# escape_uno.net
KiCad netlist of a schematic drawn in EAGLE
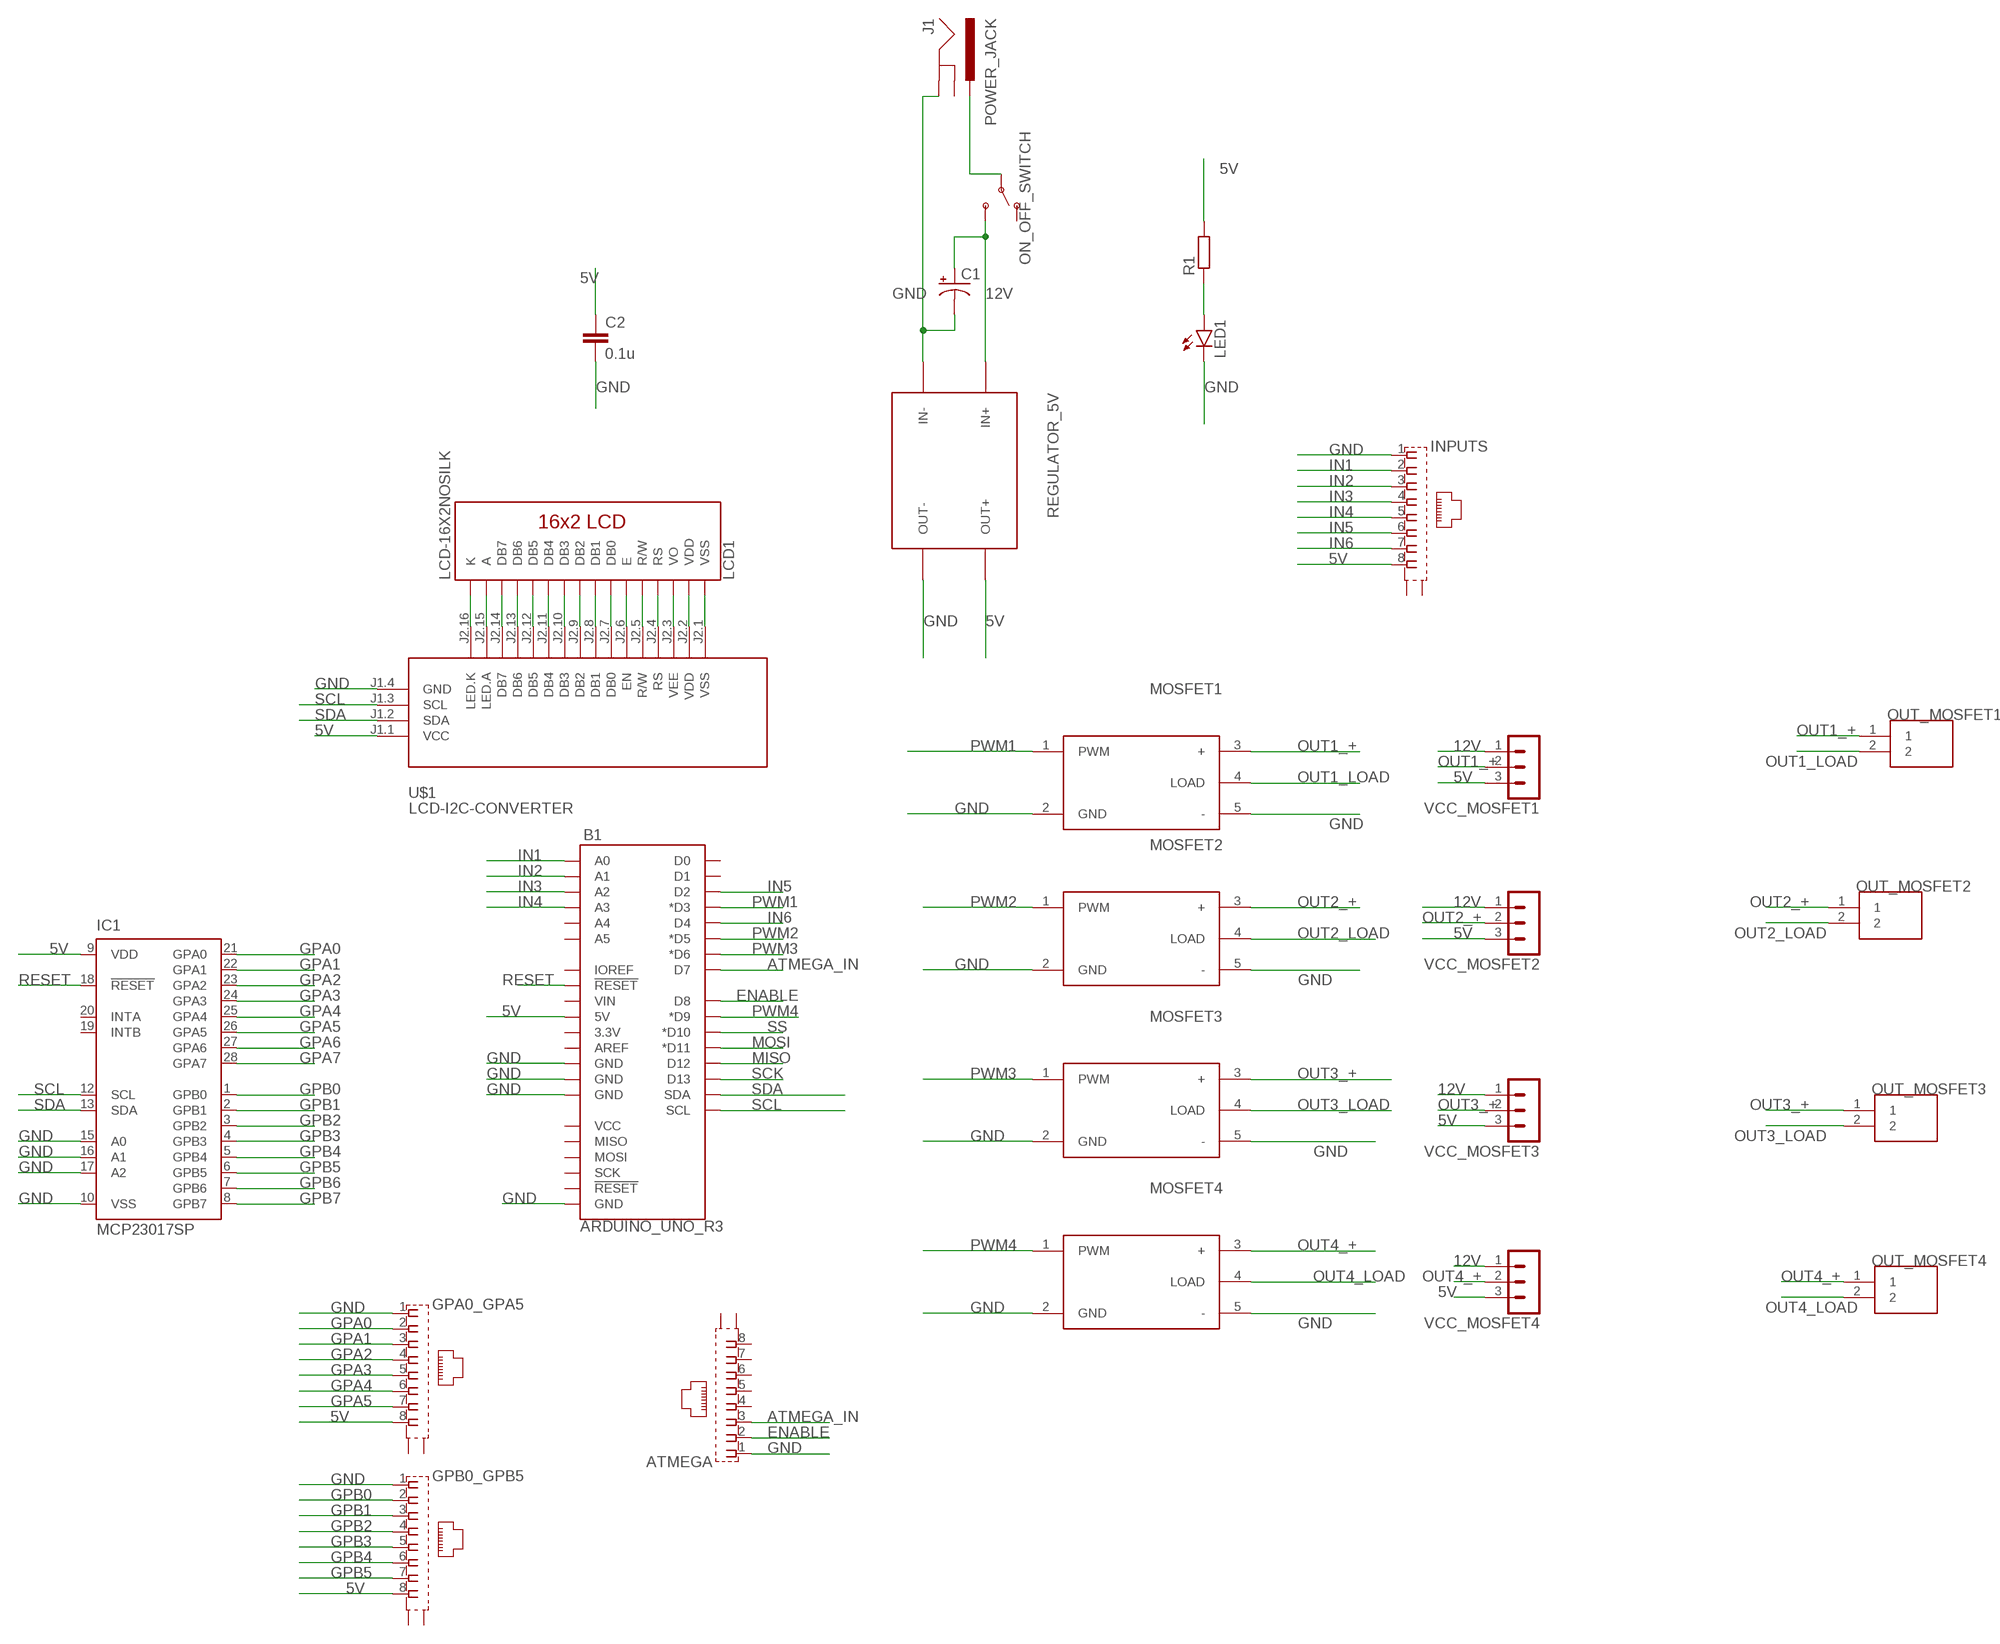
[diagram p0: schematic, sheet 1]

(export (version "E")
  (design (tool "Eeschema 10.0.6"))
  (components
    (comp (ref "ATMEGA")
      (value "GLX-S-88M")
      (footprint "eagle-import:GLX-S-88M")
      (libsource (lib "eagle-import") (part "GLX-S-88M"))
    )
    (comp (ref "B1")
      (value "ARDUINO_UNO_R3")
      (footprint "eagle-import:ARDUINO_R3")
      (libsource (lib "eagle-import") (part "ARDUINO_UNO_R3"))
    )
    (comp (ref "C1")
      (value "CPOL-USB45181C")
      (footprint "eagle-import:B45181C")
      (libsource (lib "eagle-import") (part "CPOL-USB45181C"))
    )
    (comp (ref "C2")
      (value "0.1u")
      (footprint "eagle-import:C025-025X050")
      (libsource (lib "eagle-import") (part "C-EU025-025X050"))
    )
    (comp (ref "GPA0_GPA5")
      (value "GLX-S-88M")
      (footprint "eagle-import:GLX-S-88M")
      (libsource (lib "eagle-import") (part "GLX-S-88M"))
    )
    (comp (ref "GPB0_GPB5")
      (value "GLX-S-88M")
      (footprint "eagle-import:GLX-S-88M")
      (libsource (lib "eagle-import") (part "GLX-S-88M"))
    )
    (comp (ref "IC1")
      (value "MCP23017SP")
      (footprint "eagle-import:DIL28-3")
      (fields (field (name "MF") "MICROCHIP") (field (name "MPN") "MCP23017-E/SP"))
      (libsource (lib "eagle-import") (part "MCP23017SP"))
    )
    (comp (ref "INPUTS")
      (value "GLX-S-88M")
      (footprint "eagle-import:GLX-S-88M")
      (libsource (lib "eagle-import") (part "GLX-S-88M"))
    )
    (comp (ref "J1")
      (value "POWER_JACK")
      (footprint "eagle-import:POWER_JACK_PTH")
      (libsource (lib "eagle-import") (part "POWER_JACK"))
    )
    (comp (ref "LCD1")
      (value "LCD-16X2NOSILK")
      (footprint "eagle-import:LCD-16X2_NOSILK")
      (libsource (lib "eagle-import") (part "LCD-16X2NOSILK"))
    )
    (comp (ref "LED1")
      (value "LED5MM")
      (footprint "eagle-import:LED5MM")
      (libsource (lib "eagle-import") (part "LED5MM"))
    )
    (comp (ref "MOSFET1")
      (value "SAMACSYS_PARTS_FR120N-ISOLATED-MOSFET-MOD")
      (footprint "eagle-import:SAMACSYS_PARTS_FR120N-ISOLATED-MOSFET-MOD")
      (libsource (lib "eagle-import") (part "SAMACSYS_PARTS_FR120N-ISOLATED-MOSFET-MOD"))
    )
    (comp (ref "MOSFET2")
      (value "SAMACSYS_PARTS_FR120N-ISOLATED-MOSFET-MOD")
      (footprint "eagle-import:SAMACSYS_PARTS_FR120N-ISOLATED-MOSFET-MOD")
      (libsource (lib "eagle-import") (part "SAMACSYS_PARTS_FR120N-ISOLATED-MOSFET-MOD"))
    )
    (comp (ref "MOSFET3")
      (value "SAMACSYS_PARTS_FR120N-ISOLATED-MOSFET-MOD")
      (footprint "eagle-import:SAMACSYS_PARTS_FR120N-ISOLATED-MOSFET-MOD")
      (libsource (lib "eagle-import") (part "SAMACSYS_PARTS_FR120N-ISOLATED-MOSFET-MOD"))
    )
    (comp (ref "MOSFET4")
      (value "SAMACSYS_PARTS_FR120N-ISOLATED-MOSFET-MOD")
      (footprint "eagle-import:SAMACSYS_PARTS_FR120N-ISOLATED-MOSFET-MOD")
      (libsource (lib "eagle-import") (part "SAMACSYS_PARTS_FR120N-ISOLATED-MOSFET-MOD"))
    )
    (comp (ref "ON_OFF_SWITCH")
      (value "SWITCH-SPDT-PTH-11.6X4.0MM-SHORT_LEADS")
      (footprint "eagle-import:SWITCH_SPDT_PTH_11.6X4.0MM")
      (libsource (lib "eagle-import") (part "SWITCH-SPDT-PTH-11.6X4.0MM-SHORT_LEADS"))
    )
    (comp (ref "OUT_MOSFET1")
      (value "TB006-508-02BE_TB006-508-02BE")
      (footprint "eagle-import:TB006-508-02BE_CUI_TB006-508-02BE")
      (fields (field (name "MF") "CUI Devices") (field (name "MP") "TB006-508-02BE"))
      (libsource (lib "eagle-import") (part "TB006-508-02BE_TB006-508-02BE"))
    )
    (comp (ref "OUT_MOSFET2")
      (value "TB006-508-02BE_TB006-508-02BE")
      (footprint "eagle-import:TB006-508-02BE_CUI_TB006-508-02BE")
      (fields (field (name "MF") "CUI Devices") (field (name "MP") "TB006-508-02BE"))
      (libsource (lib "eagle-import") (part "TB006-508-02BE_TB006-508-02BE"))
    )
    (comp (ref "OUT_MOSFET3")
      (value "TB006-508-02BE_TB006-508-02BE")
      (footprint "eagle-import:TB006-508-02BE_CUI_TB006-508-02BE")
      (fields (field (name "MF") "CUI Devices") (field (name "MP") "TB006-508-02BE"))
      (libsource (lib "eagle-import") (part "TB006-508-02BE_TB006-508-02BE"))
    )
    (comp (ref "OUT_MOSFET4")
      (value "TB006-508-02BE_TB006-508-02BE")
      (footprint "eagle-import:TB006-508-02BE_CUI_TB006-508-02BE")
      (fields (field (name "MF") "CUI Devices") (field (name "MP") "TB006-508-02BE"))
      (libsource (lib "eagle-import") (part "TB006-508-02BE_TB006-508-02BE"))
    )
    (comp (ref "R1")
      (value "R-EU_0207/10")
      (footprint "eagle-import:0207_10")
      (libsource (lib "eagle-import") (part "R-EU_0207/10"))
    )
    (comp (ref "REGULATOR_5V")
      (value "DIY-MODULES_DC-DC-STEP-DOWN-LM2596")
      (footprint "eagle-import:DIY-MODULES_DC-DC-STEP-DOWN-LM2596")
      (libsource (lib "eagle-import") (part "DIY-MODULES_DC-DC-STEP-DOWN-LM2596"))
    )
    (comp (ref "U$1")
      (value "LCD-I2C-CONVERTER")
      (footprint "eagle-import:LCD-I2C-CONVERTER")
      (libsource (lib "eagle-import") (part "LCD-I2C-CONVERTER"))
    )
    (comp (ref "VCC_MOSFET1")
      (value "MA03-1")
      (footprint "eagle-import:MA03-1")
      (libsource (lib "eagle-import") (part "MA03-1"))
    )
    (comp (ref "VCC_MOSFET2")
      (value "MA03-1")
      (footprint "eagle-import:MA03-1")
      (libsource (lib "eagle-import") (part "MA03-1"))
    )
    (comp (ref "VCC_MOSFET3")
      (value "MA03-1")
      (footprint "eagle-import:MA03-1")
      (libsource (lib "eagle-import") (part "MA03-1"))
    )
    (comp (ref "VCC_MOSFET4")
      (value "MA03-1")
      (footprint "eagle-import:MA03-1")
      (libsource (lib "eagle-import") (part "MA03-1"))
    )
  )
  (nets
    (net (code "1") (name "/5V") (class "Default")
      (node (ref "B1") (pin "5V") (pinfunction "5V_5V") (pintype "bidirectional"))
      (node (ref "C2") (pin "1") (pinfunction "1_1") (pintype "passive"))
      (node (ref "GPA0_GPA5") (pin "8") (pinfunction "8_8") (pintype "passive"))
      (node (ref "GPB0_GPB5") (pin "8") (pinfunction "8_8") (pintype "passive"))
      (node (ref "IC1") (pin "9") (pinfunction "VDD_9") (pintype "power_in"))
      (node (ref "INPUTS") (pin "8") (pinfunction "8_8") (pintype "passive"))
      (node (ref "R1") (pin "2") (pinfunction "2_2") (pintype "passive"))
      (node (ref "REGULATOR_5V") (pin "OUT+") (pinfunction "OUT+_OUT+") (pintype "bidirectional"))
      (node (ref "U$1") (pin "J1.1") (pinfunction "VCC_J1.1") (pintype "power_in"))
      (node (ref "VCC_MOSFET1") (pin "3") (pinfunction "3_3") (pintype "passive"))
      (node (ref "VCC_MOSFET2") (pin "3") (pinfunction "3_3") (pintype "passive"))
      (node (ref "VCC_MOSFET3") (pin "3") (pinfunction "3_3") (pintype "passive"))
      (node (ref "VCC_MOSFET4") (pin "3") (pinfunction "3_3") (pintype "passive"))
    )
    (net (code "2") (name "/12V") (class "Default")
      (node (ref "C1") (pin "+") (pinfunction "+_+") (pintype "passive"))
      (node (ref "ON_OFF_SWITCH") (pin "3") (pinfunction "S_3") (pintype "passive"))
      (node (ref "REGULATOR_5V") (pin "IN+") (pinfunction "IN+_IN+") (pintype "bidirectional"))
      (node (ref "VCC_MOSFET1") (pin "1") (pinfunction "1_1") (pintype "passive"))
      (node (ref "VCC_MOSFET2") (pin "1") (pinfunction "1_1") (pintype "passive"))
      (node (ref "VCC_MOSFET3") (pin "1") (pinfunction "1_1") (pintype "passive"))
      (node (ref "VCC_MOSFET4") (pin "1") (pinfunction "1_1") (pintype "passive"))
    )
    (net (code "3") (name "/ATMEGA_IN") (class "Default")
      (node (ref "ATMEGA") (pin "3") (pinfunction "3_3") (pintype "passive"))
      (node (ref "B1") (pin "D7") (pinfunction "D7_D7") (pintype "bidirectional"))
    )
    (net (code "4") (name "/ENABLE") (class "Default")
      (node (ref "ATMEGA") (pin "2") (pinfunction "2_2") (pintype "passive"))
      (node (ref "B1") (pin "D8") (pinfunction "D8_D8") (pintype "bidirectional"))
    )
    (net (code "5") (name "/GND") (class "Default")
      (node (ref "ATMEGA") (pin "1") (pinfunction "1_1") (pintype "passive"))
      (node (ref "B1") (pin "GND@1") (pinfunction "GND_GND@1") (pintype "bidirectional"))
      (node (ref "B1") (pin "GND@2") (pinfunction "GND_GND@2") (pintype "bidirectional"))
      (node (ref "B1") (pin "GND@3") (pinfunction "GND_GND@3") (pintype "bidirectional"))
      (node (ref "B1") (pin "GND@4") (pinfunction "GND_GND@4") (pintype "bidirectional"))
      (node (ref "C1") (pin "-") (pinfunction "-_-") (pintype "passive"))
      (node (ref "C2") (pin "2") (pinfunction "2_2") (pintype "passive"))
      (node (ref "GPA0_GPA5") (pin "1") (pinfunction "1_1") (pintype "passive"))
      (node (ref "GPB0_GPB5") (pin "1") (pinfunction "1_1") (pintype "passive"))
      (node (ref "IC1") (pin "10") (pinfunction "VSS_10") (pintype "power_in"))
      (node (ref "IC1") (pin "15") (pinfunction "A0_15") (pintype "input"))
      (node (ref "IC1") (pin "16") (pinfunction "A1_16") (pintype "input"))
      (node (ref "IC1") (pin "17") (pinfunction "A2_17") (pintype "input"))
      (node (ref "INPUTS") (pin "1") (pinfunction "1_1") (pintype "passive"))
      (node (ref "J1") (pin "GND") (pinfunction "GND_GND") (pintype "bidirectional"))
      (node (ref "LED1") (pin "K") (pinfunction "C_K") (pintype "passive"))
      (node (ref "MOSFET1") (pin "2") (pinfunction "GND_2") (pintype "bidirectional"))
      (node (ref "MOSFET1") (pin "5") (pinfunction "-_5") (pintype "bidirectional"))
      (node (ref "MOSFET2") (pin "2") (pinfunction "GND_2") (pintype "bidirectional"))
      (node (ref "MOSFET2") (pin "5") (pinfunction "-_5") (pintype "bidirectional"))
      (node (ref "MOSFET3") (pin "2") (pinfunction "GND_2") (pintype "bidirectional"))
      (node (ref "MOSFET3") (pin "5") (pinfunction "-_5") (pintype "bidirectional"))
      (node (ref "MOSFET4") (pin "2") (pinfunction "GND_2") (pintype "bidirectional"))
      (node (ref "MOSFET4") (pin "5") (pinfunction "-_5") (pintype "bidirectional"))
      (node (ref "REGULATOR_5V") (pin "IN-") (pinfunction "IN-_IN-") (pintype "bidirectional"))
      (node (ref "REGULATOR_5V") (pin "OUT-") (pinfunction "OUT-_OUT-") (pintype "bidirectional"))
      (node (ref "U$1") (pin "J1.4") (pinfunction "GND_J1.4") (pintype "power_in"))
    )
    (net (code "6") (name "/GPA0") (class "Default")
      (node (ref "GPA0_GPA5") (pin "2") (pinfunction "2_2") (pintype "passive"))
      (node (ref "IC1") (pin "21") (pinfunction "GPA0_21") (pintype "bidirectional"))
    )
    (net (code "7") (name "/GPA1") (class "Default")
      (node (ref "GPA0_GPA5") (pin "3") (pinfunction "3_3") (pintype "passive"))
      (node (ref "IC1") (pin "22") (pinfunction "GPA1_22") (pintype "bidirectional"))
    )
    (net (code "8") (name "/GPA2") (class "Default")
      (node (ref "GPA0_GPA5") (pin "4") (pinfunction "4_4") (pintype "passive"))
      (node (ref "IC1") (pin "23") (pinfunction "GPA2_23") (pintype "bidirectional"))
    )
    (net (code "9") (name "/GPA3") (class "Default")
      (node (ref "GPA0_GPA5") (pin "5") (pinfunction "5_5") (pintype "passive"))
      (node (ref "IC1") (pin "24") (pinfunction "GPA3_24") (pintype "bidirectional"))
    )
    (net (code "10") (name "/GPA4") (class "Default")
      (node (ref "GPA0_GPA5") (pin "6") (pinfunction "6_6") (pintype "passive"))
      (node (ref "IC1") (pin "25") (pinfunction "GPA4_25") (pintype "bidirectional"))
    )
    (net (code "11") (name "/GPA5") (class "Default")
      (node (ref "GPA0_GPA5") (pin "7") (pinfunction "7_7") (pintype "passive"))
      (node (ref "IC1") (pin "26") (pinfunction "GPA5_26") (pintype "bidirectional"))
    )
    (net (code "12") (name "/GPA6") (class "Default")
      (node (ref "IC1") (pin "27") (pinfunction "GPA6_27") (pintype "bidirectional"))
    )
    (net (code "13") (name "/GPA7") (class "Default")
      (node (ref "IC1") (pin "28") (pinfunction "GPA7_28") (pintype "bidirectional"))
    )
    (net (code "14") (name "/GPB0") (class "Default")
      (node (ref "GPB0_GPB5") (pin "2") (pinfunction "2_2") (pintype "passive"))
      (node (ref "IC1") (pin "1") (pinfunction "GPB0_1") (pintype "bidirectional"))
    )
    (net (code "15") (name "/GPB1") (class "Default")
      (node (ref "GPB0_GPB5") (pin "3") (pinfunction "3_3") (pintype "passive"))
      (node (ref "IC1") (pin "2") (pinfunction "GPB1_2") (pintype "bidirectional"))
    )
    (net (code "16") (name "/GPB2") (class "Default")
      (node (ref "GPB0_GPB5") (pin "4") (pinfunction "4_4") (pintype "passive"))
      (node (ref "IC1") (pin "3") (pinfunction "GPB2_3") (pintype "bidirectional"))
    )
    (net (code "17") (name "/GPB3") (class "Default")
      (node (ref "GPB0_GPB5") (pin "5") (pinfunction "5_5") (pintype "passive"))
      (node (ref "IC1") (pin "4") (pinfunction "GPB3_4") (pintype "bidirectional"))
    )
    (net (code "18") (name "/GPB4") (class "Default")
      (node (ref "GPB0_GPB5") (pin "6") (pinfunction "6_6") (pintype "passive"))
      (node (ref "IC1") (pin "5") (pinfunction "GPB4_5") (pintype "bidirectional"))
    )
    (net (code "19") (name "/GPB5") (class "Default")
      (node (ref "GPB0_GPB5") (pin "7") (pinfunction "7_7") (pintype "passive"))
      (node (ref "IC1") (pin "6") (pinfunction "GPB5_6") (pintype "bidirectional"))
    )
    (net (code "20") (name "/GPB6") (class "Default")
      (node (ref "IC1") (pin "7") (pinfunction "GPB6_7") (pintype "bidirectional"))
    )
    (net (code "21") (name "/GPB7") (class "Default")
      (node (ref "IC1") (pin "8") (pinfunction "GPB7_8") (pintype "bidirectional"))
    )
    (net (code "22") (name "/IN1") (class "Default")
      (node (ref "B1") (pin "A0") (pinfunction "A0_A0") (pintype "bidirectional"))
      (node (ref "INPUTS") (pin "2") (pinfunction "2_2") (pintype "passive"))
    )
    (net (code "23") (name "/IN2") (class "Default")
      (node (ref "B1") (pin "A1") (pinfunction "A1_A1") (pintype "bidirectional"))
      (node (ref "INPUTS") (pin "3") (pinfunction "3_3") (pintype "passive"))
    )
    (net (code "24") (name "/IN3") (class "Default")
      (node (ref "B1") (pin "A2") (pinfunction "A2_A2") (pintype "bidirectional"))
      (node (ref "INPUTS") (pin "4") (pinfunction "4_4") (pintype "passive"))
    )
    (net (code "25") (name "/IN4") (class "Default")
      (node (ref "B1") (pin "A3") (pinfunction "A3_A3") (pintype "bidirectional"))
      (node (ref "INPUTS") (pin "5") (pinfunction "5_5") (pintype "passive"))
    )
    (net (code "26") (name "/IN5") (class "Default")
      (node (ref "B1") (pin "D2") (pinfunction "D2_D2") (pintype "bidirectional"))
      (node (ref "INPUTS") (pin "6") (pinfunction "6_6") (pintype "passive"))
    )
    (net (code "27") (name "/IN6") (class "Default")
      (node (ref "B1") (pin "D4") (pinfunction "D4_D4") (pintype "bidirectional"))
      (node (ref "INPUTS") (pin "7") (pinfunction "7_7") (pintype "passive"))
    )
    (net (code "28") (name "/MISO") (class "Default")
      (node (ref "B1") (pin "D12") (pinfunction "D12_D12") (pintype "bidirectional"))
    )
    (net (code "29") (name "/MOSI") (class "Default")
      (node (ref "B1") (pin "D11") (pinfunction "*D11_D11") (pintype "bidirectional"))
    )
    (net (code "30") (name "/OUT1_+") (class "Default")
      (node (ref "MOSFET1") (pin "3") (pinfunction "+_3") (pintype "bidirectional"))
      (node (ref "OUT_MOSFET1") (pin "1") (pinfunction "1_1") (pintype "passive"))
      (node (ref "VCC_MOSFET1") (pin "2") (pinfunction "2_2") (pintype "passive"))
    )
    (net (code "31") (name "/OUT1_LOAD") (class "Default")
      (node (ref "MOSFET1") (pin "4") (pinfunction "LOAD_4") (pintype "bidirectional"))
      (node (ref "OUT_MOSFET1") (pin "2") (pinfunction "2_2") (pintype "passive"))
    )
    (net (code "32") (name "/OUT2_+") (class "Default")
      (node (ref "MOSFET2") (pin "3") (pinfunction "+_3") (pintype "bidirectional"))
      (node (ref "OUT_MOSFET2") (pin "1") (pinfunction "1_1") (pintype "passive"))
      (node (ref "VCC_MOSFET2") (pin "2") (pinfunction "2_2") (pintype "passive"))
    )
    (net (code "33") (name "/OUT2_LOAD") (class "Default")
      (node (ref "MOSFET2") (pin "4") (pinfunction "LOAD_4") (pintype "bidirectional"))
      (node (ref "OUT_MOSFET2") (pin "2") (pinfunction "2_2") (pintype "passive"))
    )
    (net (code "34") (name "/OUT3_+") (class "Default")
      (node (ref "MOSFET3") (pin "3") (pinfunction "+_3") (pintype "bidirectional"))
      (node (ref "OUT_MOSFET3") (pin "1") (pinfunction "1_1") (pintype "passive"))
      (node (ref "VCC_MOSFET3") (pin "2") (pinfunction "2_2") (pintype "passive"))
    )
    (net (code "35") (name "/OUT3_LOAD") (class "Default")
      (node (ref "MOSFET3") (pin "4") (pinfunction "LOAD_4") (pintype "bidirectional"))
      (node (ref "OUT_MOSFET3") (pin "2") (pinfunction "2_2") (pintype "passive"))
    )
    (net (code "36") (name "/OUT4_+") (class "Default")
      (node (ref "MOSFET4") (pin "3") (pinfunction "+_3") (pintype "bidirectional"))
      (node (ref "OUT_MOSFET4") (pin "1") (pinfunction "1_1") (pintype "passive"))
      (node (ref "VCC_MOSFET4") (pin "2") (pinfunction "2_2") (pintype "passive"))
    )
    (net (code "37") (name "/OUT4_LOAD") (class "Default")
      (node (ref "MOSFET4") (pin "4") (pinfunction "LOAD_4") (pintype "bidirectional"))
      (node (ref "OUT_MOSFET4") (pin "2") (pinfunction "2_2") (pintype "passive"))
    )
    (net (code "38") (name "/PWM1") (class "Default")
      (node (ref "B1") (pin "D3") (pinfunction "*D3_D3") (pintype "bidirectional"))
      (node (ref "MOSFET1") (pin "1") (pinfunction "PWM_1") (pintype "bidirectional"))
    )
    (net (code "39") (name "/PWM2") (class "Default")
      (node (ref "B1") (pin "D5") (pinfunction "*D5_D5") (pintype "bidirectional"))
      (node (ref "MOSFET2") (pin "1") (pinfunction "PWM_1") (pintype "bidirectional"))
    )
    (net (code "40") (name "/PWM3") (class "Default")
      (node (ref "B1") (pin "D6") (pinfunction "*D6_D6") (pintype "bidirectional"))
      (node (ref "MOSFET3") (pin "1") (pinfunction "PWM_1") (pintype "bidirectional"))
    )
    (net (code "41") (name "/PWM4") (class "Default")
      (node (ref "B1") (pin "D9") (pinfunction "*D9_D9") (pintype "bidirectional"))
      (node (ref "MOSFET4") (pin "1") (pinfunction "PWM_1") (pintype "bidirectional"))
    )
    (net (code "42") (name "/RESET") (class "Default")
      (node (ref "B1") (pin "RESET@1") (pinfunction "~{RESET}_RESET@1") (pintype "bidirectional"))
      (node (ref "IC1") (pin "18") (pinfunction "~{RESET}_18") (pintype "input"))
    )
    (net (code "43") (name "/SCK") (class "Default")
      (node (ref "B1") (pin "D13") (pinfunction "D13_D13") (pintype "bidirectional"))
    )
    (net (code "44") (name "/SCL") (class "Default")
      (node (ref "B1") (pin "SCL") (pinfunction "SCL_SCL") (pintype "bidirectional"))
      (node (ref "IC1") (pin "12") (pinfunction "SCL_12") (pintype "input"))
      (node (ref "U$1") (pin "J1.3") (pinfunction "SCL_J1.3") (pintype "bidirectional"))
    )
    (net (code "45") (name "/SDA") (class "Default")
      (node (ref "B1") (pin "SDA") (pinfunction "SDA_SDA") (pintype "bidirectional"))
      (node (ref "IC1") (pin "13") (pinfunction "SDA_13") (pintype "bidirectional"))
      (node (ref "U$1") (pin "J1.2") (pinfunction "SDA_J1.2") (pintype "bidirectional"))
    )
    (net (code "46") (name "/SS") (class "Default")
      (node (ref "B1") (pin "D10") (pinfunction "*D10_D10") (pintype "bidirectional"))
    )
    (net (code "47") (name "Net-(LCD1-A)") (class "Default")
      (node (ref "LCD1") (pin "15") (pinfunction "A_15") (pintype "power_in"))
      (node (ref "U$1") (pin "J2.15") (pinfunction "LED.A_J2.15") (pintype "bidirectional"))
    )
    (net (code "48") (name "Net-(LCD1-DB0)") (class "Default")
      (node (ref "LCD1") (pin "7") (pinfunction "DB0_7") (pintype "bidirectional"))
      (node (ref "U$1") (pin "J2.7") (pinfunction "DB0_J2.7") (pintype "bidirectional"))
    )
    (net (code "49") (name "Net-(LCD1-DB1)") (class "Default")
      (node (ref "LCD1") (pin "8") (pinfunction "DB1_8") (pintype "bidirectional"))
      (node (ref "U$1") (pin "J2.8") (pinfunction "DB1_J2.8") (pintype "bidirectional"))
    )
    (net (code "50") (name "Net-(LCD1-DB2)") (class "Default")
      (node (ref "LCD1") (pin "9") (pinfunction "DB2_9") (pintype "bidirectional"))
      (node (ref "U$1") (pin "J2.9") (pinfunction "DB2_J2.9") (pintype "bidirectional"))
    )
    (net (code "51") (name "Net-(LCD1-DB3)") (class "Default")
      (node (ref "LCD1") (pin "10") (pinfunction "DB3_10") (pintype "bidirectional"))
      (node (ref "U$1") (pin "J2.10") (pinfunction "DB3_J2.10") (pintype "bidirectional"))
    )
    (net (code "52") (name "Net-(LCD1-DB4)") (class "Default")
      (node (ref "LCD1") (pin "11") (pinfunction "DB4_11") (pintype "bidirectional"))
      (node (ref "U$1") (pin "J2.11") (pinfunction "DB4_J2.11") (pintype "bidirectional"))
    )
    (net (code "53") (name "Net-(LCD1-DB5)") (class "Default")
      (node (ref "LCD1") (pin "12") (pinfunction "DB5_12") (pintype "bidirectional"))
      (node (ref "U$1") (pin "J2.12") (pinfunction "DB5_J2.12") (pintype "bidirectional"))
    )
    (net (code "54") (name "Net-(LCD1-DB6)") (class "Default")
      (node (ref "LCD1") (pin "13") (pinfunction "DB6_13") (pintype "bidirectional"))
      (node (ref "U$1") (pin "J2.13") (pinfunction "DB6_J2.13") (pintype "bidirectional"))
    )
    (net (code "55") (name "Net-(LCD1-DB7)") (class "Default")
      (node (ref "LCD1") (pin "14") (pinfunction "DB7_14") (pintype "bidirectional"))
      (node (ref "U$1") (pin "J2.14") (pinfunction "DB7_J2.14") (pintype "bidirectional"))
    )
    (net (code "56") (name "Net-(LCD1-E)") (class "Default")
      (node (ref "LCD1") (pin "6") (pinfunction "E_6") (pintype "input"))
      (node (ref "U$1") (pin "J2.6") (pinfunction "EN_J2.6") (pintype "bidirectional"))
    )
    (net (code "57") (name "Net-(LCD1-K)") (class "Default")
      (node (ref "LCD1") (pin "16") (pinfunction "K_16") (pintype "power_in"))
      (node (ref "U$1") (pin "J2.16") (pinfunction "LED.K_J2.16") (pintype "bidirectional"))
    )
    (net (code "58") (name "Net-(LCD1-RS)") (class "Default")
      (node (ref "LCD1") (pin "4") (pinfunction "RS_4") (pintype "input"))
      (node (ref "U$1") (pin "J2.4") (pinfunction "RS_J2.4") (pintype "bidirectional"))
    )
    (net (code "59") (name "Net-(LCD1-R{slash}W)") (class "Default")
      (node (ref "LCD1") (pin "5") (pinfunction "R/W_5") (pintype "input"))
      (node (ref "U$1") (pin "J2.5") (pinfunction "R/W_J2.5") (pintype "bidirectional"))
    )
    (net (code "60") (name "Net-(LCD1-VDD)") (class "Default")
      (node (ref "LCD1") (pin "2") (pinfunction "VDD_2") (pintype "power_in"))
      (node (ref "U$1") (pin "J2.2") (pinfunction "VDD_J2.2") (pintype "bidirectional"))
    )
    (net (code "61") (name "Net-(LCD1-VO)") (class "Default")
      (node (ref "LCD1") (pin "3") (pinfunction "VO_3") (pintype "bidirectional"))
      (node (ref "U$1") (pin "J2.3") (pinfunction "VEE_J2.3") (pintype "bidirectional"))
    )
    (net (code "62") (name "Net-(LCD1-VSS)") (class "Default")
      (node (ref "LCD1") (pin "1") (pinfunction "VSS_1") (pintype "power_in"))
      (node (ref "U$1") (pin "J2.1") (pinfunction "VSS_J2.1") (pintype "bidirectional"))
    )
    (net (code "63") (name "Net-(LED1-PadA)") (class "Default")
      (node (ref "LED1") (pin "A") (pinfunction "A_A") (pintype "passive"))
      (node (ref "R1") (pin "1") (pinfunction "1_1") (pintype "passive"))
    )
    (net (code "64") (name "Net-(ON_OFF_SWITCH-P)") (class "Default")
      (node (ref "J1") (pin "PWR") (pinfunction "PWR_PWR") (pintype "bidirectional"))
      (node (ref "ON_OFF_SWITCH") (pin "2") (pinfunction "P_2") (pintype "passive"))
    )
    (net (code "65") (name "unconnected-(ATMEGA-Pad4)") (class "Default")
      (node (ref "ATMEGA") (pin "4") (pinfunction "4_4") (pintype "passive"))
    )
    (net (code "66") (name "unconnected-(ATMEGA-Pad5)") (class "Default")
      (node (ref "ATMEGA") (pin "5") (pinfunction "5_5") (pintype "passive"))
    )
    (net (code "67") (name "unconnected-(ATMEGA-Pad6)") (class "Default")
      (node (ref "ATMEGA") (pin "6") (pinfunction "6_6") (pintype "passive"))
    )
    (net (code "68") (name "unconnected-(ATMEGA-Pad7)") (class "Default")
      (node (ref "ATMEGA") (pin "7") (pinfunction "7_7") (pintype "passive"))
    )
    (net (code "69") (name "unconnected-(ATMEGA-Pad8)") (class "Default")
      (node (ref "ATMEGA") (pin "8") (pinfunction "8_8") (pintype "passive"))
    )
    (net (code "70") (name "unconnected-(ATMEGA-PadS1)") (class "Default")
      (node (ref "ATMEGA") (pin "S1") (pinfunction "S1_S1") (pintype "passive"))
    )
    (net (code "71") (name "unconnected-(ATMEGA-PadS2)") (class "Default")
      (node (ref "ATMEGA") (pin "S2") (pinfunction "S2_S2") (pintype "passive"))
    )
    (net (code "72") (name "unconnected-(B1-Pad3.3V)") (class "Default")
      (node (ref "B1") (pin "3.3V") (pinfunction "3.3V_3.3V") (pintype "bidirectional"))
    )
    (net (code "73") (name "unconnected-(B1-PadA4)") (class "Default")
      (node (ref "B1") (pin "A4") (pinfunction "A4_A4") (pintype "bidirectional"))
    )
    (net (code "74") (name "unconnected-(B1-PadA5)") (class "Default")
      (node (ref "B1") (pin "A5") (pinfunction "A5_A5") (pintype "bidirectional"))
    )
    (net (code "75") (name "unconnected-(B1-PadAREF)") (class "Default")
      (node (ref "B1") (pin "AREF") (pinfunction "AREF_AREF") (pintype "bidirectional"))
    )
    (net (code "76") (name "unconnected-(B1-PadD0)") (class "Default")
      (node (ref "B1") (pin "D0") (pinfunction "D0_D0") (pintype "bidirectional"))
    )
    (net (code "77") (name "unconnected-(B1-PadD1)") (class "Default")
      (node (ref "B1") (pin "D1") (pinfunction "D1_D1") (pintype "bidirectional"))
    )
    (net (code "78") (name "unconnected-(B1-PadIOREF)") (class "Default")
      (node (ref "B1") (pin "IOREF") (pinfunction "IOREF_IOREF") (pintype "bidirectional"))
    )
    (net (code "79") (name "unconnected-(B1-PadMISO)") (class "Default")
      (node (ref "B1") (pin "MISO") (pinfunction "MISO_MISO") (pintype "bidirectional"))
    )
    (net (code "80") (name "unconnected-(B1-PadMOSI)") (class "Default")
      (node (ref "B1") (pin "MOSI") (pinfunction "MOSI_MOSI") (pintype "bidirectional"))
    )
    (net (code "81") (name "unconnected-(B1-PadSCK)") (class "Default")
      (node (ref "B1") (pin "SCK") (pinfunction "SCK_SCK") (pintype "bidirectional"))
    )
    (net (code "82") (name "unconnected-(B1-PadVCC)") (class "Default")
      (node (ref "B1") (pin "VCC") (pinfunction "VCC_VCC") (pintype "bidirectional"))
    )
    (net (code "83") (name "unconnected-(B1-PadVIN)") (class "Default")
      (node (ref "B1") (pin "VIN") (pinfunction "VIN_VIN") (pintype "bidirectional"))
    )
    (net (code "84") (name "unconnected-(B1-~{RESET}-PadRESET@2)") (class "Default")
      (node (ref "B1") (pin "RESET@2") (pinfunction "~{RESET}_RESET@2") (pintype "bidirectional"))
    )
    (net (code "85") (name "unconnected-(GPA0_GPA5-PadS1)") (class "Default")
      (node (ref "GPA0_GPA5") (pin "S1") (pinfunction "S1_S1") (pintype "passive"))
    )
    (net (code "86") (name "unconnected-(GPA0_GPA5-PadS2)") (class "Default")
      (node (ref "GPA0_GPA5") (pin "S2") (pinfunction "S2_S2") (pintype "passive"))
    )
    (net (code "87") (name "unconnected-(GPB0_GPB5-PadS1)") (class "Default")
      (node (ref "GPB0_GPB5") (pin "S1") (pinfunction "S1_S1") (pintype "passive"))
    )
    (net (code "88") (name "unconnected-(GPB0_GPB5-PadS2)") (class "Default")
      (node (ref "GPB0_GPB5") (pin "S2") (pinfunction "S2_S2") (pintype "passive"))
    )
    (net (code "89") (name "unconnected-(IC1-INTA-Pad20)") (class "Default")
      (node (ref "IC1") (pin "20") (pinfunction "INTA_20") (pintype "output"))
    )
    (net (code "90") (name "unconnected-(IC1-INTB-Pad19)") (class "Default")
      (node (ref "IC1") (pin "19") (pinfunction "INTB_19") (pintype "output"))
    )
    (net (code "91") (name "unconnected-(INPUTS-PadS1)") (class "Default")
      (node (ref "INPUTS") (pin "S1") (pinfunction "S1_S1") (pintype "passive"))
    )
    (net (code "92") (name "unconnected-(INPUTS-PadS2)") (class "Default")
      (node (ref "INPUTS") (pin "S2") (pinfunction "S2_S2") (pintype "passive"))
    )
    (net (code "93") (name "unconnected-(J1-PadGNDBREAK)") (class "Default")
      (node (ref "J1") (pin "GNDBREAK") (pinfunction "GNDBREAK_GNDBREAK") (pintype "bidirectional"))
    )
    (net (code "94") (name "unconnected-(ON_OFF_SWITCH-O-Pad1)") (class "Default")
      (node (ref "ON_OFF_SWITCH") (pin "1") (pinfunction "O_1") (pintype "passive"))
    )
  )
)
